# v1_2SMD.net
KiCad netlist of a schematic drawn in EAGLE
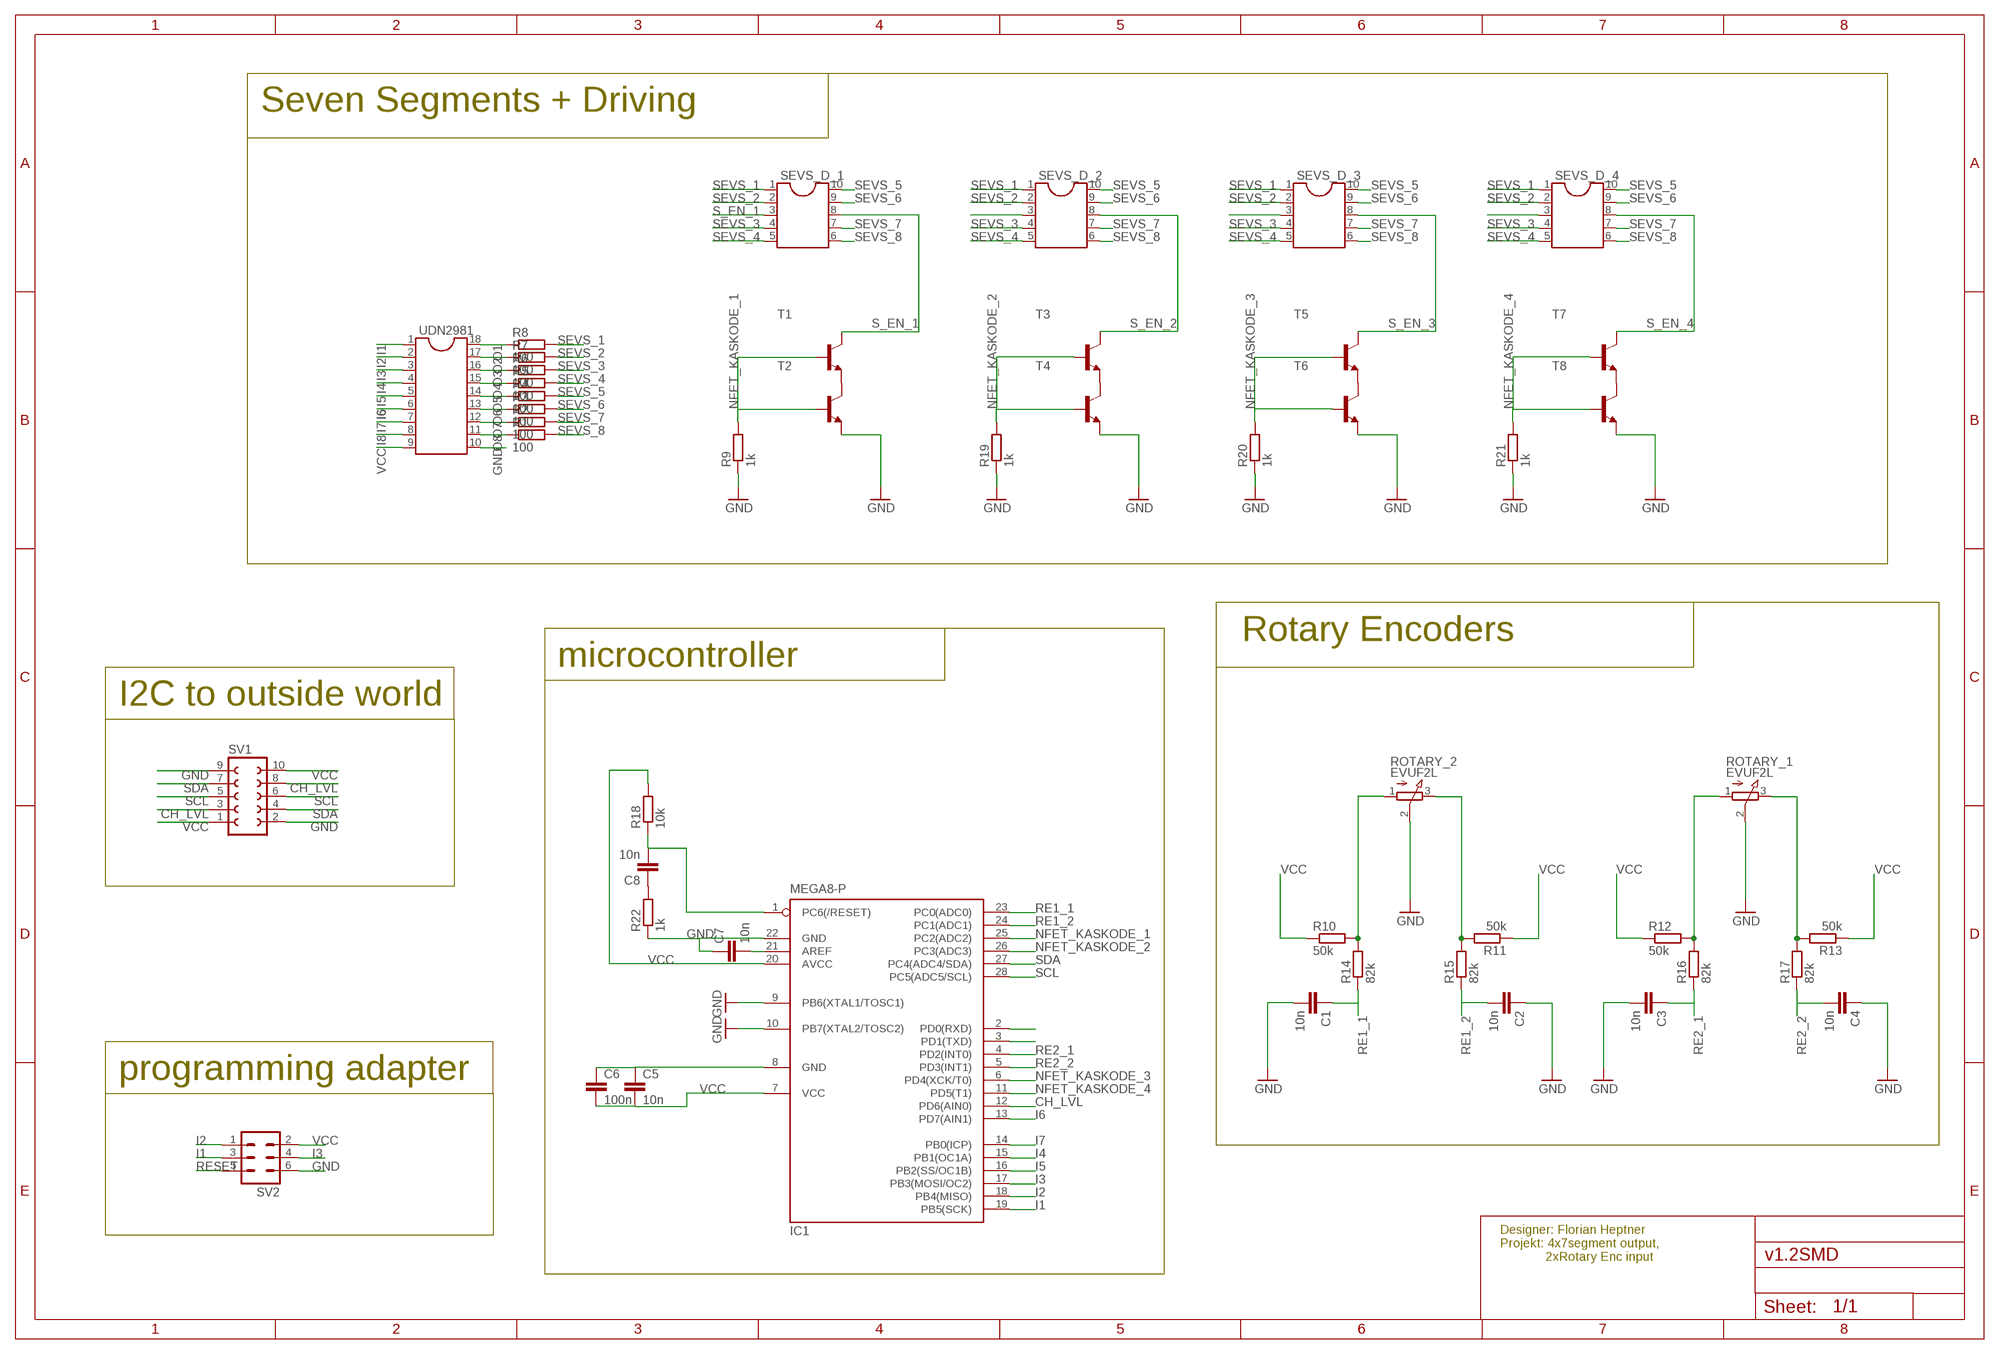
[diagram p0: schematic, sheet 1]

(export (version "E")
  (design (tool "Eeschema 10.0.6"))
  (components
    (comp (ref "C1")
      (value "10n")
      (footprint "eagle-import:C0603")
      (libsource (lib "eagle-import") (part "C-EUC0603"))
    )
    (comp (ref "C2")
      (value "10n")
      (footprint "eagle-import:C0603")
      (libsource (lib "eagle-import") (part "C-EUC0603"))
    )
    (comp (ref "C3")
      (value "10n")
      (footprint "eagle-import:C0603")
      (libsource (lib "eagle-import") (part "C-EUC0603"))
    )
    (comp (ref "C4")
      (value "10n")
      (footprint "eagle-import:C0603")
      (libsource (lib "eagle-import") (part "C-EUC0603"))
    )
    (comp (ref "C5")
      (value "10n")
      (footprint "eagle-import:C0603")
      (libsource (lib "eagle-import") (part "C-EUC0603"))
    )
    (comp (ref "C6")
      (value "100n")
      (footprint "eagle-import:C0603")
      (libsource (lib "eagle-import") (part "C-EUC0603"))
    )
    (comp (ref "C7")
      (value "10n")
      (footprint "eagle-import:C0603")
      (libsource (lib "eagle-import") (part "C-EUC0603"))
    )
    (comp (ref "C8")
      (value "10n")
      (footprint "eagle-import:C0603")
      (libsource (lib "eagle-import") (part "C-EUC0603"))
    )
    (comp (ref "IC1")
      (value "MEGA8-P")
      (footprint "eagle-import:DIL28-3")
      (libsource (lib "eagle-import") (part "MEGA8-P"))
    )
    (comp (ref "R1")
      (value "100")
      (footprint "eagle-import:R0603")
      (libsource (lib "eagle-import") (part "R-EU_R0603"))
    )
    (comp (ref "R2")
      (value "100")
      (footprint "eagle-import:R0603")
      (libsource (lib "eagle-import") (part "R-EU_R0603"))
    )
    (comp (ref "R3")
      (value "100")
      (footprint "eagle-import:R0603")
      (libsource (lib "eagle-import") (part "R-EU_R0603"))
    )
    (comp (ref "R4")
      (value "100")
      (footprint "eagle-import:R0603")
      (libsource (lib "eagle-import") (part "R-EU_R0603"))
    )
    (comp (ref "R5")
      (value "100")
      (footprint "eagle-import:R0603")
      (libsource (lib "eagle-import") (part "R-EU_R0603"))
    )
    (comp (ref "R6")
      (value "100")
      (footprint "eagle-import:R0603")
      (libsource (lib "eagle-import") (part "R-EU_R0603"))
    )
    (comp (ref "R7")
      (value "100")
      (footprint "eagle-import:R0603")
      (libsource (lib "eagle-import") (part "R-EU_R0603"))
    )
    (comp (ref "R8")
      (value "100")
      (footprint "eagle-import:R0603")
      (libsource (lib "eagle-import") (part "R-EU_R0603"))
    )
    (comp (ref "R9")
      (value "1k")
      (footprint "eagle-import:R0603")
      (libsource (lib "eagle-import") (part "R-EU_R0603"))
    )
    (comp (ref "R10")
      (value "50k")
      (footprint "eagle-import:R0603")
      (libsource (lib "eagle-import") (part "R-EU_R0603"))
    )
    (comp (ref "R11")
      (value "50k")
      (footprint "eagle-import:R0603")
      (libsource (lib "eagle-import") (part "R-EU_R0603"))
    )
    (comp (ref "R12")
      (value "50k")
      (footprint "eagle-import:R0603")
      (libsource (lib "eagle-import") (part "R-EU_R0603"))
    )
    (comp (ref "R13")
      (value "50k")
      (footprint "eagle-import:R0603")
      (libsource (lib "eagle-import") (part "R-EU_R0603"))
    )
    (comp (ref "R14")
      (value "82k")
      (footprint "eagle-import:R0603")
      (libsource (lib "eagle-import") (part "R-EU_R0603"))
    )
    (comp (ref "R15")
      (value "82k")
      (footprint "eagle-import:R0603")
      (libsource (lib "eagle-import") (part "R-EU_R0603"))
    )
    (comp (ref "R16")
      (value "82k")
      (footprint "eagle-import:R0603")
      (libsource (lib "eagle-import") (part "R-EU_R0603"))
    )
    (comp (ref "R17")
      (value "82k")
      (footprint "eagle-import:R0603")
      (libsource (lib "eagle-import") (part "R-EU_R0603"))
    )
    (comp (ref "R18")
      (value "10k")
      (footprint "eagle-import:R0603")
      (libsource (lib "eagle-import") (part "R-EU_R0603"))
    )
    (comp (ref "R19")
      (value "1k")
      (footprint "eagle-import:R0603")
      (libsource (lib "eagle-import") (part "R-EU_R0603"))
    )
    (comp (ref "R20")
      (value "1k")
      (footprint "eagle-import:R0603")
      (libsource (lib "eagle-import") (part "R-EU_R0603"))
    )
    (comp (ref "R21")
      (value "1k")
      (footprint "eagle-import:R0603")
      (libsource (lib "eagle-import") (part "R-EU_R0603"))
    )
    (comp (ref "R22")
      (value "1k")
      (footprint "eagle-import:R0603")
      (libsource (lib "eagle-import") (part "R-EU_R0603"))
    )
    (comp (ref "ROTARY_1")
      (value "EVUF2L")
      (footprint "eagle-import:EVUFXL")
      (libsource (lib "eagle-import") (part "EVULF2"))
    )
    (comp (ref "ROTARY_2")
      (value "EVUF2L")
      (footprint "eagle-import:EVUFXL")
      (libsource (lib "eagle-import") (part "EVULF2"))
    )
    (comp (ref "SEVS_D_1")
      (value "DIL10")
      (footprint "eagle-import:DIL10")
      (libsource (lib "eagle-import") (part "DIL10"))
    )
    (comp (ref "SEVS_D_2")
      (value "DIL10")
      (footprint "eagle-import:DIL10")
      (libsource (lib "eagle-import") (part "DIL10"))
    )
    (comp (ref "SEVS_D_3")
      (value "DIL10")
      (footprint "eagle-import:DIL10")
      (libsource (lib "eagle-import") (part "DIL10"))
    )
    (comp (ref "SEVS_D_4")
      (value "DIL10")
      (footprint "eagle-import:DIL10")
      (libsource (lib "eagle-import") (part "DIL10"))
    )
    (comp (ref "SV1")
      (value "FE05-2")
      (footprint "eagle-import:FE05-2")
      (libsource (lib "eagle-import") (part "FE05-2"))
    )
    (comp (ref "SV2")
      (value "ML6")
      (footprint "eagle-import:ML6")
      (libsource (lib "eagle-import") (part "ML6"))
    )
    (comp (ref "T1")
      (value "BC808-NPN-SOT23-BEC")
      (footprint "eagle-import:SOT23-BEC")
      (libsource (lib "eagle-import") (part "-NPN-SOT23-BECBC808"))
    )
    (comp (ref "T2")
      (value "BC808-NPN-SOT23-BEC")
      (footprint "eagle-import:SOT23-BEC")
      (libsource (lib "eagle-import") (part "-NPN-SOT23-BECBC808"))
    )
    (comp (ref "T3")
      (value "BC808-NPN-SOT23-BEC")
      (footprint "eagle-import:SOT23-BEC")
      (libsource (lib "eagle-import") (part "-NPN-SOT23-BECBC808"))
    )
    (comp (ref "T4")
      (value "BC808-NPN-SOT23-BEC")
      (footprint "eagle-import:SOT23-BEC")
      (libsource (lib "eagle-import") (part "-NPN-SOT23-BECBC808"))
    )
    (comp (ref "T5")
      (value "BC808-NPN-SOT23-BEC")
      (footprint "eagle-import:SOT23-BEC")
      (libsource (lib "eagle-import") (part "-NPN-SOT23-BECBC808"))
    )
    (comp (ref "T6")
      (value "BC808-NPN-SOT23-BEC")
      (footprint "eagle-import:SOT23-BEC")
      (libsource (lib "eagle-import") (part "-NPN-SOT23-BECBC808"))
    )
    (comp (ref "T7")
      (value "BC808-NPN-SOT23-BEC")
      (footprint "eagle-import:SOT23-BEC")
      (libsource (lib "eagle-import") (part "-NPN-SOT23-BECBC808"))
    )
    (comp (ref "T8")
      (value "BC808-NPN-SOT23-BEC")
      (footprint "eagle-import:SOT23-BEC")
      (libsource (lib "eagle-import") (part "-NPN-SOT23-BECBC808"))
    )
    (comp (ref "UDN2981")
      (value "DIL18")
      (footprint "eagle-import:DIL18")
      (libsource (lib "eagle-import") (part "DIL18"))
    )
  )
  (nets
    (net (code "1") (name "/CH_LVL") (class "Default")
      (node (ref "IC1") (pin "12") (pinfunction "PD6(AIN0)_12") (pintype "bidirectional"))
      (node (ref "SV1") (pin "3") (pinfunction "3_3") (pintype "passive"))
      (node (ref "SV1") (pin "8") (pinfunction "8_8") (pintype "passive"))
    )
    (net (code "2") (name "/I1") (class "Default")
      (node (ref "IC1") (pin "19") (pinfunction "PB5(SCK)_19") (pintype "bidirectional"))
      (node (ref "SV2") (pin "3") (pinfunction "3_3") (pintype "passive"))
      (node (ref "UDN2981") (pin "1") (pinfunction "1_1") (pintype "passive"))
    )
    (net (code "3") (name "/I2") (class "Default")
      (node (ref "IC1") (pin "18") (pinfunction "PB4(MISO)_18") (pintype "bidirectional"))
      (node (ref "SV2") (pin "1") (pinfunction "1_1") (pintype "passive"))
      (node (ref "UDN2981") (pin "2") (pinfunction "2_2") (pintype "passive"))
    )
    (net (code "4") (name "/I3") (class "Default")
      (node (ref "IC1") (pin "17") (pinfunction "PB3(MOSI/OC2)_17") (pintype "bidirectional"))
      (node (ref "SV2") (pin "4") (pinfunction "4_4") (pintype "passive"))
      (node (ref "UDN2981") (pin "3") (pinfunction "3_3") (pintype "passive"))
    )
    (net (code "5") (name "/I4") (class "Default")
      (node (ref "IC1") (pin "15") (pinfunction "PB1(OC1A)_15") (pintype "bidirectional"))
      (node (ref "UDN2981") (pin "4") (pinfunction "4_4") (pintype "passive"))
    )
    (net (code "6") (name "/I5") (class "Default")
      (node (ref "IC1") (pin "16") (pinfunction "PB2(SS/OC1B)_16") (pintype "bidirectional"))
      (node (ref "UDN2981") (pin "5") (pinfunction "5_5") (pintype "passive"))
    )
    (net (code "7") (name "/I6") (class "Default")
      (node (ref "IC1") (pin "13") (pinfunction "PD7(AIN1)_13") (pintype "bidirectional"))
      (node (ref "UDN2981") (pin "6") (pinfunction "6_6") (pintype "passive"))
    )
    (net (code "8") (name "/I7") (class "Default")
      (node (ref "IC1") (pin "14") (pinfunction "PB0(ICP)_14") (pintype "bidirectional"))
      (node (ref "UDN2981") (pin "7") (pinfunction "7_7") (pintype "passive"))
    )
    (net (code "9") (name "/I8") (class "Default")
      (node (ref "UDN2981") (pin "8") (pinfunction "8_8") (pintype "passive"))
    )
    (net (code "10") (name "/NFET_KASKODE_1") (class "Default")
      (node (ref "IC1") (pin "25") (pinfunction "PC2(ADC2)_25") (pintype "bidirectional"))
      (node (ref "R9") (pin "2") (pinfunction "2_2") (pintype "passive"))
      (node (ref "T1") (pin "B") (pinfunction "B_B") (pintype "passive"))
      (node (ref "T2") (pin "B") (pinfunction "B_B") (pintype "passive"))
    )
    (net (code "11") (name "/NFET_KASKODE_2") (class "Default")
      (node (ref "IC1") (pin "26") (pinfunction "PC3(ADC3)_26") (pintype "bidirectional"))
      (node (ref "R19") (pin "2") (pinfunction "2_2") (pintype "passive"))
      (node (ref "T3") (pin "B") (pinfunction "B_B") (pintype "passive"))
      (node (ref "T4") (pin "B") (pinfunction "B_B") (pintype "passive"))
    )
    (net (code "12") (name "/NFET_KASKODE_3") (class "Default")
      (node (ref "IC1") (pin "6") (pinfunction "PD4(XCK/T0)_6") (pintype "bidirectional"))
      (node (ref "R20") (pin "2") (pinfunction "2_2") (pintype "passive"))
      (node (ref "T5") (pin "B") (pinfunction "B_B") (pintype "passive"))
      (node (ref "T6") (pin "B") (pinfunction "B_B") (pintype "passive"))
    )
    (net (code "13") (name "/NFET_KASKODE_4") (class "Default")
      (node (ref "IC1") (pin "11") (pinfunction "PD5(T1)_11") (pintype "bidirectional"))
      (node (ref "R21") (pin "2") (pinfunction "2_2") (pintype "passive"))
      (node (ref "T7") (pin "B") (pinfunction "B_B") (pintype "passive"))
      (node (ref "T8") (pin "B") (pinfunction "B_B") (pintype "passive"))
    )
    (net (code "14") (name "/O1") (class "Default")
      (node (ref "R8") (pin "1") (pinfunction "1_1") (pintype "passive"))
      (node (ref "UDN2981") (pin "18") (pinfunction "18_18") (pintype "passive"))
    )
    (net (code "15") (name "/O2") (class "Default")
      (node (ref "R7") (pin "1") (pinfunction "1_1") (pintype "passive"))
      (node (ref "UDN2981") (pin "17") (pinfunction "17_17") (pintype "passive"))
    )
    (net (code "16") (name "/O3") (class "Default")
      (node (ref "R6") (pin "1") (pinfunction "1_1") (pintype "passive"))
      (node (ref "UDN2981") (pin "16") (pinfunction "16_16") (pintype "passive"))
    )
    (net (code "17") (name "/O4") (class "Default")
      (node (ref "R5") (pin "1") (pinfunction "1_1") (pintype "passive"))
      (node (ref "UDN2981") (pin "15") (pinfunction "15_15") (pintype "passive"))
    )
    (net (code "18") (name "/O5") (class "Default")
      (node (ref "R4") (pin "1") (pinfunction "1_1") (pintype "passive"))
      (node (ref "UDN2981") (pin "14") (pinfunction "14_14") (pintype "passive"))
    )
    (net (code "19") (name "/O6") (class "Default")
      (node (ref "R3") (pin "1") (pinfunction "1_1") (pintype "passive"))
      (node (ref "UDN2981") (pin "13") (pinfunction "13_13") (pintype "passive"))
    )
    (net (code "20") (name "/O7") (class "Default")
      (node (ref "R2") (pin "1") (pinfunction "1_1") (pintype "passive"))
      (node (ref "UDN2981") (pin "12") (pinfunction "12_12") (pintype "passive"))
    )
    (net (code "21") (name "/O8") (class "Default")
      (node (ref "R1") (pin "1") (pinfunction "1_1") (pintype "passive"))
      (node (ref "UDN2981") (pin "11") (pinfunction "11_11") (pintype "passive"))
    )
    (net (code "22") (name "/RE1_1") (class "Default")
      (node (ref "C1") (pin "1") (pinfunction "1_1") (pintype "passive"))
      (node (ref "IC1") (pin "23") (pinfunction "PC0(ADC0)_23") (pintype "bidirectional"))
      (node (ref "R14") (pin "1") (pinfunction "1_1") (pintype "passive"))
    )
    (net (code "23") (name "/RE1_2") (class "Default")
      (node (ref "C2") (pin "2") (pinfunction "2_2") (pintype "passive"))
      (node (ref "IC1") (pin "24") (pinfunction "PC1(ADC1)_24") (pintype "bidirectional"))
      (node (ref "R15") (pin "1") (pinfunction "1_1") (pintype "passive"))
    )
    (net (code "24") (name "/RE2_1") (class "Default")
      (node (ref "C3") (pin "1") (pinfunction "1_1") (pintype "passive"))
      (node (ref "IC1") (pin "4") (pinfunction "PD2(INT0)_4") (pintype "bidirectional"))
      (node (ref "R16") (pin "1") (pinfunction "1_1") (pintype "passive"))
    )
    (net (code "25") (name "/RE2_2") (class "Default")
      (node (ref "C4") (pin "2") (pinfunction "2_2") (pintype "passive"))
      (node (ref "IC1") (pin "5") (pinfunction "PD3(INT1)_5") (pintype "bidirectional"))
      (node (ref "R17") (pin "1") (pinfunction "1_1") (pintype "passive"))
    )
    (net (code "26") (name "/RESET") (class "Default")
      (node (ref "C8") (pin "2") (pinfunction "2_2") (pintype "passive"))
      (node (ref "IC1") (pin "1") (pinfunction "PC6(/RESET)_1") (pintype "bidirectional"))
      (node (ref "R18") (pin "1") (pinfunction "1_1") (pintype "passive"))
      (node (ref "SV2") (pin "5") (pinfunction "5_5") (pintype "passive"))
    )
    (net (code "27") (name "/SCL") (class "Default")
      (node (ref "IC1") (pin "28") (pinfunction "PC5(ADC5/SCL)_28") (pintype "bidirectional"))
      (node (ref "SV1") (pin "5") (pinfunction "5_5") (pintype "passive"))
      (node (ref "SV1") (pin "6") (pinfunction "6_6") (pintype "passive"))
    )
    (net (code "28") (name "/SDA") (class "Default")
      (node (ref "IC1") (pin "27") (pinfunction "PC4(ADC4/SDA)_27") (pintype "bidirectional"))
      (node (ref "SV1") (pin "4") (pinfunction "4_4") (pintype "passive"))
      (node (ref "SV1") (pin "7") (pinfunction "7_7") (pintype "passive"))
    )
    (net (code "29") (name "/SEVS_1") (class "Default")
      (node (ref "R8") (pin "2") (pinfunction "2_2") (pintype "passive"))
      (node (ref "SEVS_D_1") (pin "1") (pinfunction "1_1") (pintype "passive"))
      (node (ref "SEVS_D_2") (pin "1") (pinfunction "1_1") (pintype "passive"))
      (node (ref "SEVS_D_3") (pin "1") (pinfunction "1_1") (pintype "passive"))
      (node (ref "SEVS_D_4") (pin "1") (pinfunction "1_1") (pintype "passive"))
    )
    (net (code "30") (name "/SEVS_2") (class "Default")
      (node (ref "R7") (pin "2") (pinfunction "2_2") (pintype "passive"))
      (node (ref "SEVS_D_1") (pin "2") (pinfunction "2_2") (pintype "passive"))
      (node (ref "SEVS_D_2") (pin "2") (pinfunction "2_2") (pintype "passive"))
      (node (ref "SEVS_D_3") (pin "2") (pinfunction "2_2") (pintype "passive"))
      (node (ref "SEVS_D_4") (pin "2") (pinfunction "2_2") (pintype "passive"))
    )
    (net (code "31") (name "/SEVS_3") (class "Default")
      (node (ref "R6") (pin "2") (pinfunction "2_2") (pintype "passive"))
      (node (ref "SEVS_D_1") (pin "4") (pinfunction "4_4") (pintype "passive"))
      (node (ref "SEVS_D_2") (pin "4") (pinfunction "4_4") (pintype "passive"))
      (node (ref "SEVS_D_3") (pin "4") (pinfunction "4_4") (pintype "passive"))
      (node (ref "SEVS_D_4") (pin "4") (pinfunction "4_4") (pintype "passive"))
    )
    (net (code "32") (name "/SEVS_4") (class "Default")
      (node (ref "R5") (pin "2") (pinfunction "2_2") (pintype "passive"))
      (node (ref "SEVS_D_1") (pin "5") (pinfunction "5_5") (pintype "passive"))
      (node (ref "SEVS_D_2") (pin "5") (pinfunction "5_5") (pintype "passive"))
      (node (ref "SEVS_D_3") (pin "5") (pinfunction "5_5") (pintype "passive"))
      (node (ref "SEVS_D_4") (pin "5") (pinfunction "5_5") (pintype "passive"))
    )
    (net (code "33") (name "/SEVS_5") (class "Default")
      (node (ref "R4") (pin "2") (pinfunction "2_2") (pintype "passive"))
      (node (ref "SEVS_D_1") (pin "10") (pinfunction "10_10") (pintype "passive"))
      (node (ref "SEVS_D_2") (pin "10") (pinfunction "10_10") (pintype "passive"))
      (node (ref "SEVS_D_3") (pin "10") (pinfunction "10_10") (pintype "passive"))
      (node (ref "SEVS_D_4") (pin "10") (pinfunction "10_10") (pintype "passive"))
    )
    (net (code "34") (name "/SEVS_6") (class "Default")
      (node (ref "R3") (pin "2") (pinfunction "2_2") (pintype "passive"))
      (node (ref "SEVS_D_1") (pin "9") (pinfunction "9_9") (pintype "passive"))
      (node (ref "SEVS_D_2") (pin "9") (pinfunction "9_9") (pintype "passive"))
      (node (ref "SEVS_D_3") (pin "9") (pinfunction "9_9") (pintype "passive"))
      (node (ref "SEVS_D_4") (pin "9") (pinfunction "9_9") (pintype "passive"))
    )
    (net (code "35") (name "/SEVS_7") (class "Default")
      (node (ref "R2") (pin "2") (pinfunction "2_2") (pintype "passive"))
      (node (ref "SEVS_D_1") (pin "7") (pinfunction "7_7") (pintype "passive"))
      (node (ref "SEVS_D_2") (pin "7") (pinfunction "7_7") (pintype "passive"))
      (node (ref "SEVS_D_3") (pin "7") (pinfunction "7_7") (pintype "passive"))
      (node (ref "SEVS_D_4") (pin "7") (pinfunction "7_7") (pintype "passive"))
    )
    (net (code "36") (name "/SEVS_8") (class "Default")
      (node (ref "R1") (pin "2") (pinfunction "2_2") (pintype "passive"))
      (node (ref "SEVS_D_1") (pin "6") (pinfunction "6_6") (pintype "passive"))
      (node (ref "SEVS_D_2") (pin "6") (pinfunction "6_6") (pintype "passive"))
      (node (ref "SEVS_D_3") (pin "6") (pinfunction "6_6") (pintype "passive"))
      (node (ref "SEVS_D_4") (pin "6") (pinfunction "6_6") (pintype "passive"))
    )
    (net (code "37") (name "/S_EN_1") (class "Default")
      (node (ref "SEVS_D_1") (pin "3") (pinfunction "3_3") (pintype "passive"))
      (node (ref "SEVS_D_1") (pin "8") (pinfunction "8_8") (pintype "passive"))
      (node (ref "T1") (pin "C") (pinfunction "C_C") (pintype "passive"))
    )
    (net (code "38") (name "/S_EN_2") (class "Default")
      (node (ref "SEVS_D_2") (pin "3") (pinfunction "3_3") (pintype "passive"))
      (node (ref "SEVS_D_2") (pin "8") (pinfunction "8_8") (pintype "passive"))
      (node (ref "T3") (pin "C") (pinfunction "C_C") (pintype "passive"))
    )
    (net (code "39") (name "/S_EN_3") (class "Default")
      (node (ref "SEVS_D_3") (pin "3") (pinfunction "3_3") (pintype "passive"))
      (node (ref "SEVS_D_3") (pin "8") (pinfunction "8_8") (pintype "passive"))
      (node (ref "T5") (pin "C") (pinfunction "C_C") (pintype "passive"))
    )
    (net (code "40") (name "/S_EN_4") (class "Default")
      (node (ref "SEVS_D_4") (pin "3") (pinfunction "3_3") (pintype "passive"))
      (node (ref "SEVS_D_4") (pin "8") (pinfunction "8_8") (pintype "passive"))
      (node (ref "T7") (pin "C") (pinfunction "C_C") (pintype "passive"))
    )
    (net (code "41") (name "/VCC") (class "Default")
      (node (ref "C5") (pin "2") (pinfunction "2_2") (pintype "passive"))
      (node (ref "C6") (pin "2") (pinfunction "2_2") (pintype "passive"))
      (node (ref "IC1") (pin "20") (pinfunction "AVCC_20") (pintype "power_in"))
      (node (ref "IC1") (pin "7") (pinfunction "VCC_7") (pintype "power_in"))
      (node (ref "R10") (pin "1") (pinfunction "1_1") (pintype "passive"))
      (node (ref "R11") (pin "1") (pinfunction "1_1") (pintype "passive"))
      (node (ref "R12") (pin "1") (pinfunction "1_1") (pintype "passive"))
      (node (ref "R13") (pin "1") (pinfunction "1_1") (pintype "passive"))
      (node (ref "R18") (pin "2") (pinfunction "2_2") (pintype "passive"))
      (node (ref "SV1") (pin "1") (pinfunction "1_1") (pintype "passive"))
      (node (ref "SV1") (pin "10") (pinfunction "10_10") (pintype "passive"))
      (node (ref "SV2") (pin "2") (pinfunction "2_2") (pintype "passive"))
      (node (ref "UDN2981") (pin "9") (pinfunction "9_9") (pintype "passive"))
    )
    (net (code "42") (name "GND") (class "Default")
      (node (ref "C1") (pin "2") (pinfunction "2_2") (pintype "passive"))
      (node (ref "C2") (pin "1") (pinfunction "1_1") (pintype "passive"))
      (node (ref "C3") (pin "2") (pinfunction "2_2") (pintype "passive"))
      (node (ref "C4") (pin "1") (pinfunction "1_1") (pintype "passive"))
      (node (ref "C7") (pin "1") (pinfunction "1_1") (pintype "passive"))
      (node (ref "IC1") (pin "10") (pinfunction "PB7(XTAL2/TOSC2)_10") (pintype "bidirectional"))
      (node (ref "IC1") (pin "22") (pinfunction "GND_22") (pintype "power_in"))
      (node (ref "IC1") (pin "9") (pinfunction "PB6(XTAL1/TOSC1)_9") (pintype "bidirectional"))
      (node (ref "R19") (pin "1") (pinfunction "1_1") (pintype "passive"))
      (node (ref "R20") (pin "1") (pinfunction "1_1") (pintype "passive"))
      (node (ref "R21") (pin "1") (pinfunction "1_1") (pintype "passive"))
      (node (ref "R22") (pin "1") (pinfunction "1_1") (pintype "passive"))
      (node (ref "R9") (pin "1") (pinfunction "1_1") (pintype "passive"))
      (node (ref "ROTARY_1") (pin "2") (pinfunction "S_2") (pintype "passive"))
      (node (ref "ROTARY_2") (pin "2") (pinfunction "S_2") (pintype "passive"))
      (node (ref "SV1") (pin "2") (pinfunction "2_2") (pintype "passive"))
      (node (ref "SV1") (pin "9") (pinfunction "9_9") (pintype "passive"))
      (node (ref "SV2") (pin "6") (pinfunction "6_6") (pintype "passive"))
      (node (ref "T2") (pin "E") (pinfunction "E_E") (pintype "passive"))
      (node (ref "T4") (pin "E") (pinfunction "E_E") (pintype "passive"))
      (node (ref "T6") (pin "E") (pinfunction "E_E") (pintype "passive"))
      (node (ref "T8") (pin "E") (pinfunction "E_E") (pintype "passive"))
      (node (ref "UDN2981") (pin "10") (pinfunction "10_10") (pintype "passive"))
    )
    (net (code "43") (name "Net-(C5-Pad1)") (class "Default")
      (node (ref "C5") (pin "1") (pinfunction "1_1") (pintype "passive"))
      (node (ref "C6") (pin "1") (pinfunction "1_1") (pintype "passive"))
      (node (ref "IC1") (pin "8") (pinfunction "GND_8") (pintype "power_in"))
    )
    (net (code "44") (name "Net-(C8-Pad1)") (class "Default")
      (node (ref "C8") (pin "1") (pinfunction "1_1") (pintype "passive"))
      (node (ref "R22") (pin "2") (pinfunction "2_2") (pintype "passive"))
    )
    (net (code "45") (name "Net-(IC1-AREF)") (class "Default")
      (node (ref "C7") (pin "2") (pinfunction "2_2") (pintype "passive"))
      (node (ref "IC1") (pin "21") (pinfunction "AREF_21") (pintype "passive"))
    )
    (net (code "46") (name "Net-(ROTARY_1-A)") (class "Default")
      (node (ref "R12") (pin "2") (pinfunction "2_2") (pintype "passive"))
      (node (ref "R16") (pin "2") (pinfunction "2_2") (pintype "passive"))
      (node (ref "ROTARY_1") (pin "1") (pinfunction "A_1") (pintype "passive"))
    )
    (net (code "47") (name "Net-(ROTARY_1-E)") (class "Default")
      (node (ref "R13") (pin "2") (pinfunction "2_2") (pintype "passive"))
      (node (ref "R17") (pin "2") (pinfunction "2_2") (pintype "passive"))
      (node (ref "ROTARY_1") (pin "3") (pinfunction "E_3") (pintype "passive"))
    )
    (net (code "48") (name "Net-(ROTARY_2-A)") (class "Default")
      (node (ref "R10") (pin "2") (pinfunction "2_2") (pintype "passive"))
      (node (ref "R14") (pin "2") (pinfunction "2_2") (pintype "passive"))
      (node (ref "ROTARY_2") (pin "1") (pinfunction "A_1") (pintype "passive"))
    )
    (net (code "49") (name "Net-(ROTARY_2-E)") (class "Default")
      (node (ref "R11") (pin "2") (pinfunction "2_2") (pintype "passive"))
      (node (ref "R15") (pin "2") (pinfunction "2_2") (pintype "passive"))
      (node (ref "ROTARY_2") (pin "3") (pinfunction "E_3") (pintype "passive"))
    )
    (net (code "50") (name "Net-(T1-PadE)") (class "Default")
      (node (ref "T1") (pin "E") (pinfunction "E_E") (pintype "passive"))
      (node (ref "T2") (pin "C") (pinfunction "C_C") (pintype "passive"))
    )
    (net (code "51") (name "Net-(T3-PadE)") (class "Default")
      (node (ref "T3") (pin "E") (pinfunction "E_E") (pintype "passive"))
      (node (ref "T4") (pin "C") (pinfunction "C_C") (pintype "passive"))
    )
    (net (code "52") (name "Net-(T5-PadE)") (class "Default")
      (node (ref "T5") (pin "E") (pinfunction "E_E") (pintype "passive"))
      (node (ref "T6") (pin "C") (pinfunction "C_C") (pintype "passive"))
    )
    (net (code "53") (name "Net-(T7-PadE)") (class "Default")
      (node (ref "T7") (pin "E") (pinfunction "E_E") (pintype "passive"))
      (node (ref "T8") (pin "C") (pinfunction "C_C") (pintype "passive"))
    )
    (net (code "54") (name "unconnected-(IC1-PD0(RXD)-Pad2)") (class "Default")
      (node (ref "IC1") (pin "2") (pinfunction "PD0(RXD)_2") (pintype "bidirectional"))
    )
    (net (code "55") (name "unconnected-(IC1-PD1(TXD)-Pad3)") (class "Default")
      (node (ref "IC1") (pin "3") (pinfunction "PD1(TXD)_3") (pintype "bidirectional"))
    )
  )
)
